# 1-Schematic_SIT210_PCB.net
KiCad netlist of a schematic drawn in EasyEDA
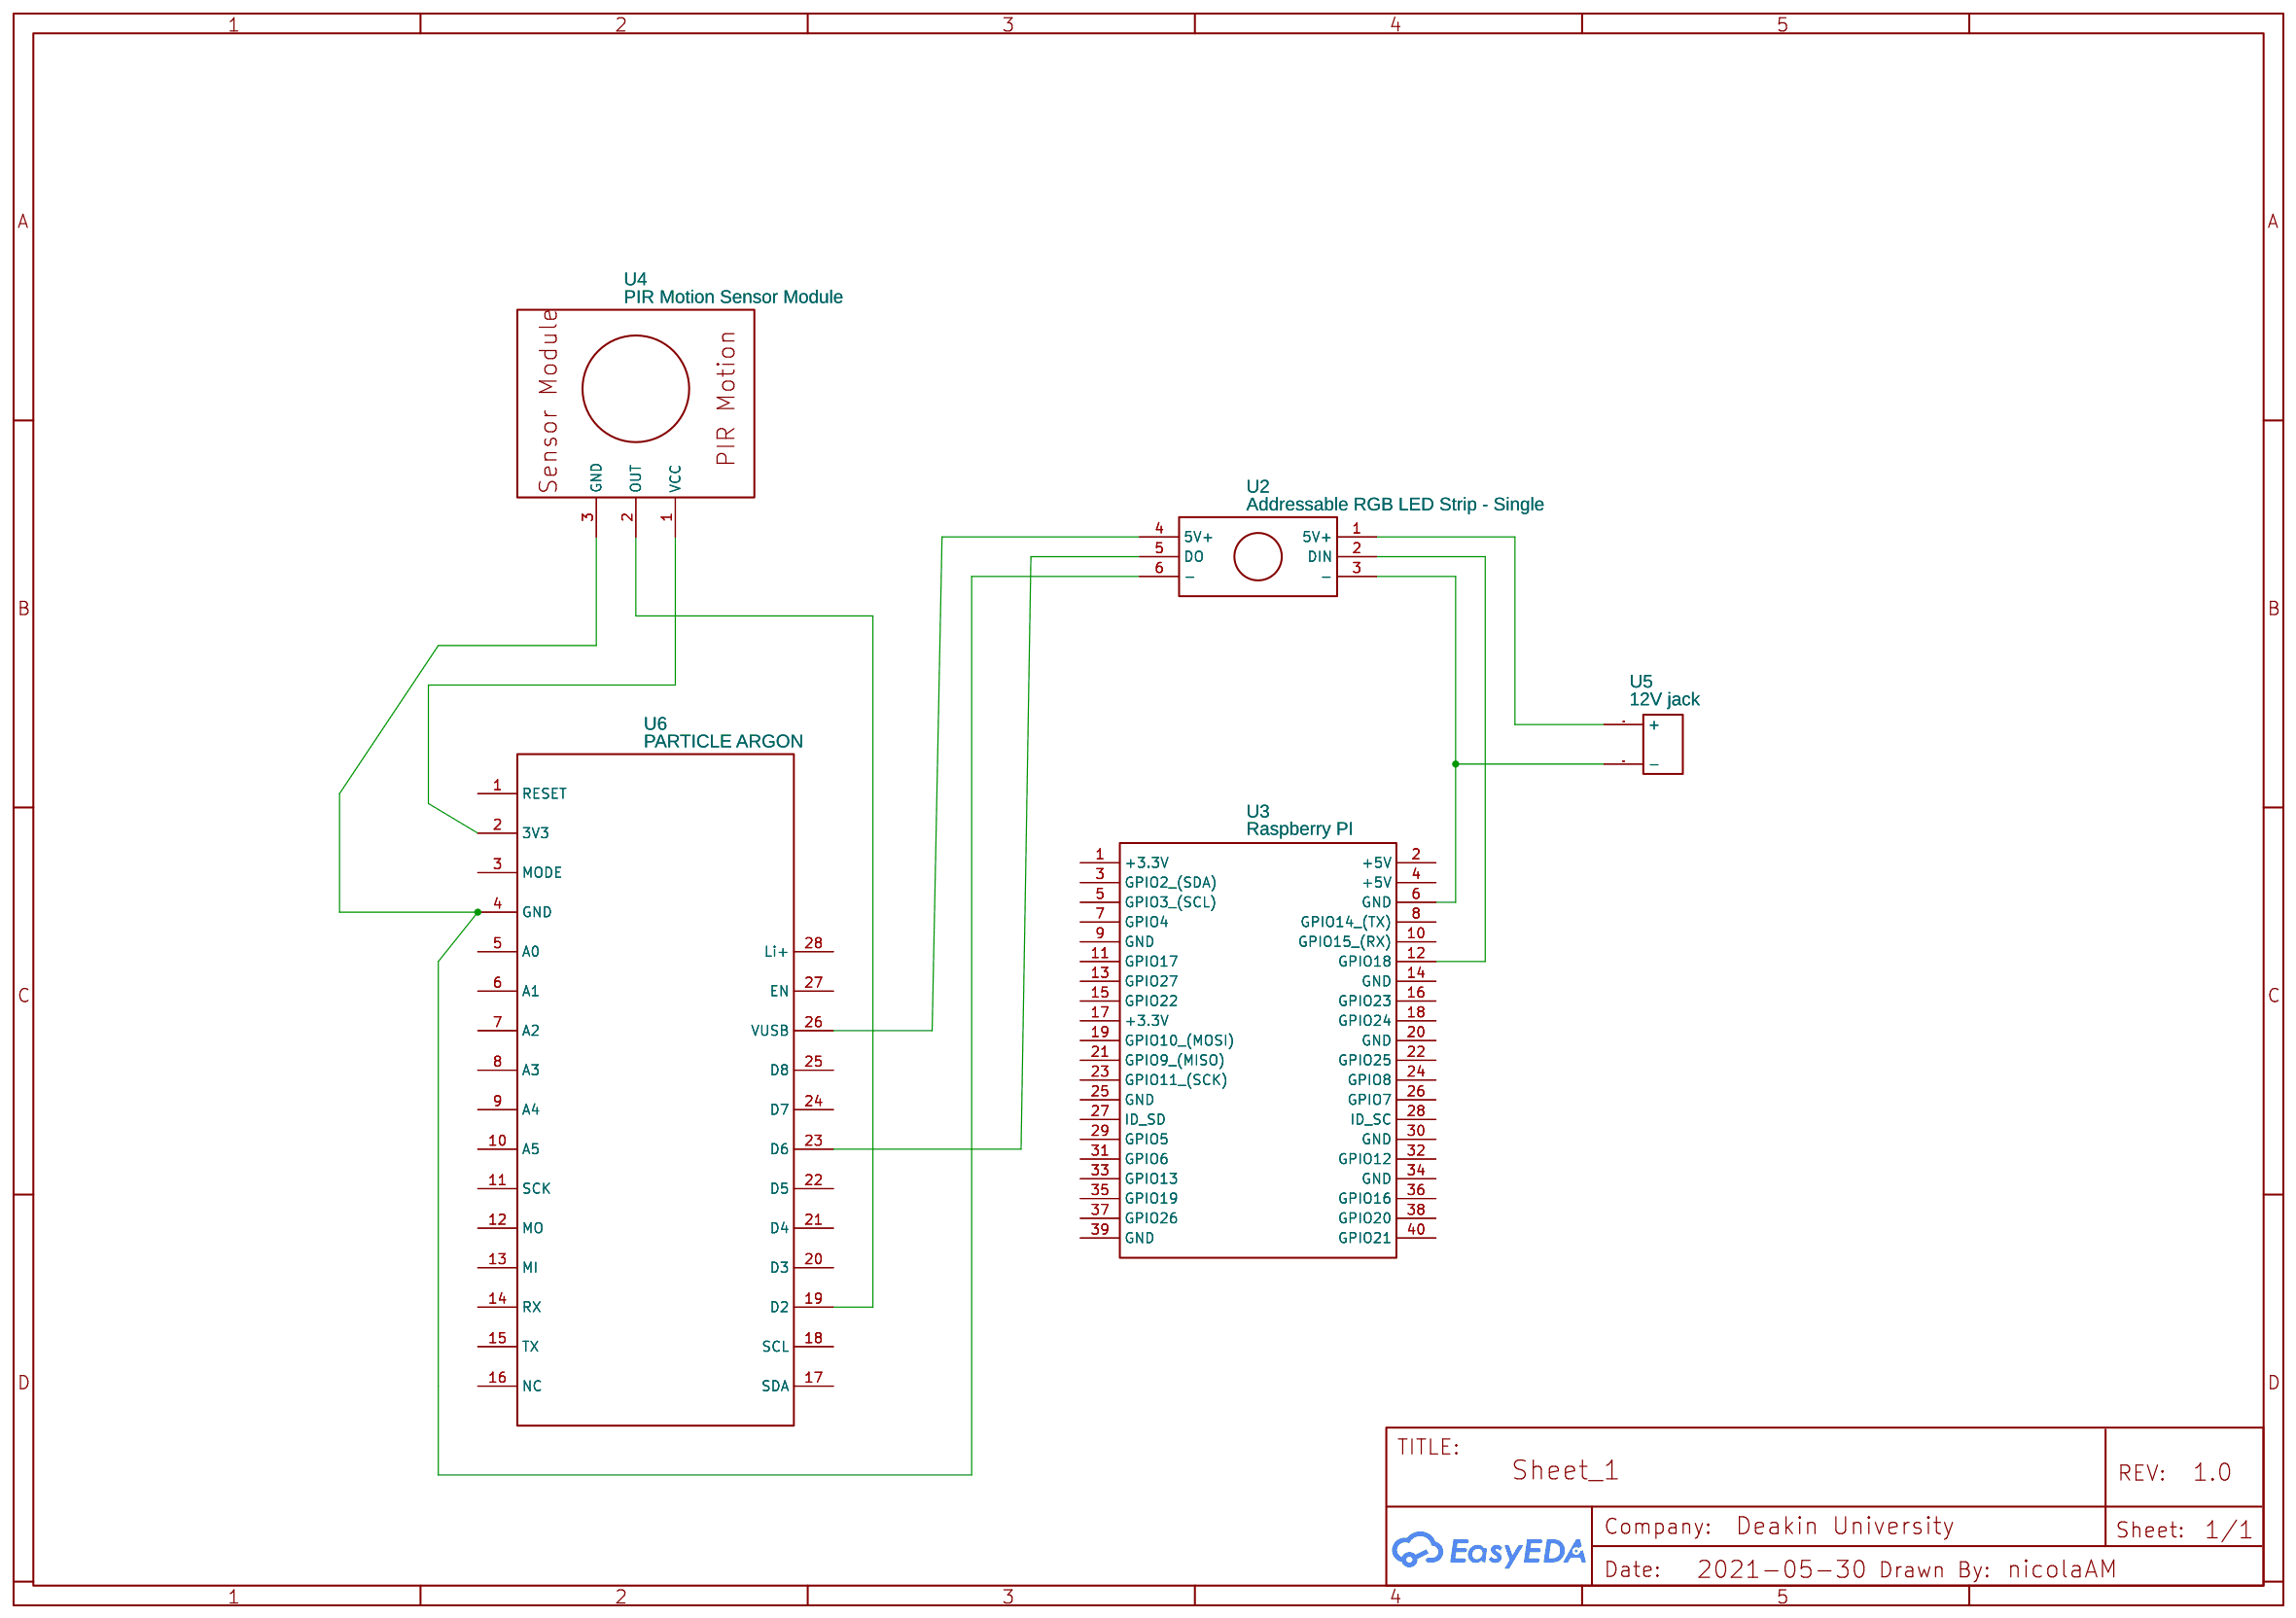
[diagram p0: schematic sheet]

(export (version "E")
  (design (tool "Eeschema 10.0.6"))
  (components
    (comp (ref "U2")
      (value "Addressable RGB LED Strip - Single")
      (libsource (lib "") (part "Addressable RGB LED Strip - Single"))
    )
    (comp (ref "U3") (value "Raspberry PI") (libsource (lib "") (part "Raspberry PI")))
    (comp (ref "U4")
      (value "PIR Motion Sensor Module")
      (libsource (lib "") (part "PIR Motion Sensor Module"))
    )
    (comp (ref "U5") (value "12V jack") (libsource (lib "") (part "12V jack")))
    (comp (ref "U6") (value "PARTICLE ARGON") (libsource (lib "") (part "PARTICLE ARGON")))
  )
  (nets
    (net (code "1") (name "Net-(U2-DIN)") (class "Default")
      (node (ref "U2") (pin "2") (pinfunction "DIN_2") (pintype "input"))
      (node (ref "U3") (pin "12") (pinfunction "GPIO18_12") (pintype "unspecified"))
    )
    (net (code "2") (name "Net-(U2-DO)") (class "Default")
      (node (ref "U2") (pin "5") (pinfunction "DO_5") (pintype "output"))
      (node (ref "U6") (pin "23") (pinfunction "D6_23") (pintype "unspecified"))
    )
    (net (code "3") (name "Net-(U4-GND)") (class "Default")
      (node (ref "U2") (pin "6") (pinfunction "-_6") (pintype "passive"))
      (node (ref "U4") (pin "3") (pinfunction "GND_3") (pintype "unspecified"))
      (node (ref "U6") (pin "4") (pinfunction "GND_4") (pintype "unspecified"))
    )
    (net (code "4") (name "Net-(U4-OUT)") (class "Default")
      (node (ref "U4") (pin "2") (pinfunction "OUT_2") (pintype "unspecified"))
      (node (ref "U6") (pin "19") (pinfunction "D2_19") (pintype "unspecified"))
    )
    (net (code "5") (name "Net-(U4-VCC)") (class "Default")
      (node (ref "U4") (pin "1") (pinfunction "VCC_1") (pintype "unspecified"))
      (node (ref "U6") (pin "2") (pinfunction "3V3_2") (pintype "unspecified"))
    )
    (net (code "6") (name "Net-(U5-+)") (class "Default")
      (node (ref "U2") (pin "1") (pinfunction "5V+_1") (pintype "passive"))
      (node (ref "U5") (pin "Vcc") (pinfunction "+_Vcc") (pintype "unspecified"))
    )
    (net (code "7") (name "Net-(U5--)") (class "Default")
      (node (ref "U2") (pin "3") (pinfunction "-_3") (pintype "passive"))
      (node (ref "U3") (pin "6") (pinfunction "GND_6") (pintype "passive"))
      (node (ref "U5") (pin "GND") (pinfunction "-_GND") (pintype "unspecified"))
    )
    (net (code "8") (name "Net-(U6-VUSB)") (class "Default")
      (node (ref "U2") (pin "4") (pinfunction "5V+_4") (pintype "passive"))
      (node (ref "U6") (pin "26") (pinfunction "VUSB_26") (pintype "unspecified"))
    )
    (net (code "9") (name "unconnected-(U3-+3.3V-Pad1)") (class "Default")
      (node (ref "U3") (pin "1") (pinfunction "+3.3V_1") (pintype "passive"))
    )
    (net (code "10") (name "unconnected-(U3-+3.3V-Pad17)") (class "Default")
      (node (ref "U3") (pin "17") (pinfunction "+3.3V_17") (pintype "passive"))
    )
    (net (code "11") (name "unconnected-(U3-+5V-Pad2)") (class "Default")
      (node (ref "U3") (pin "2") (pinfunction "+5V_2") (pintype "passive"))
    )
    (net (code "12") (name "unconnected-(U3-+5V-Pad4)") (class "Default")
      (node (ref "U3") (pin "4") (pinfunction "+5V_4") (pintype "passive"))
    )
    (net (code "13") (name "unconnected-(U3-GND-Pad9)") (class "Default")
      (node (ref "U3") (pin "9") (pinfunction "GND_9") (pintype "passive"))
    )
    (net (code "14") (name "unconnected-(U3-GND-Pad14)") (class "Default")
      (node (ref "U3") (pin "14") (pinfunction "GND_14") (pintype "passive"))
    )
    (net (code "15") (name "unconnected-(U3-GND-Pad20)") (class "Default")
      (node (ref "U3") (pin "20") (pinfunction "GND_20") (pintype "passive"))
    )
    (net (code "16") (name "unconnected-(U3-GND-Pad25)") (class "Default")
      (node (ref "U3") (pin "25") (pinfunction "GND_25") (pintype "passive"))
    )
    (net (code "17") (name "unconnected-(U3-GND-Pad30)") (class "Default")
      (node (ref "U3") (pin "30") (pinfunction "GND_30") (pintype "passive"))
    )
    (net (code "18") (name "unconnected-(U3-GND-Pad34)") (class "Default")
      (node (ref "U3") (pin "34") (pinfunction "GND_34") (pintype "passive"))
    )
    (net (code "19") (name "unconnected-(U3-GND-Pad39)") (class "Default")
      (node (ref "U3") (pin "39") (pinfunction "GND_39") (pintype "passive"))
    )
    (net (code "20") (name "unconnected-(U3-GPIO2_(SDA)-Pad3)") (class "Default")
      (node (ref "U3") (pin "3") (pinfunction "GPIO2_(SDA)_3") (pintype "unspecified"))
    )
    (net (code "21") (name "unconnected-(U3-GPIO3_(SCL)-Pad5)") (class "Default")
      (node (ref "U3") (pin "5") (pinfunction "GPIO3_(SCL)_5") (pintype "unspecified"))
    )
    (net (code "22") (name "unconnected-(U3-GPIO4-Pad7)") (class "Default")
      (node (ref "U3") (pin "7") (pinfunction "GPIO4_7") (pintype "unspecified"))
    )
    (net (code "23") (name "unconnected-(U3-GPIO5-Pad29)") (class "Default")
      (node (ref "U3") (pin "29") (pinfunction "GPIO5_29") (pintype "unspecified"))
    )
    (net (code "24") (name "unconnected-(U3-GPIO6-Pad31)") (class "Default")
      (node (ref "U3") (pin "31") (pinfunction "GPIO6_31") (pintype "unspecified"))
    )
    (net (code "25") (name "unconnected-(U3-GPIO7-Pad26)") (class "Default")
      (node (ref "U3") (pin "26") (pinfunction "GPIO7_26") (pintype "unspecified"))
    )
    (net (code "26") (name "unconnected-(U3-GPIO8-Pad24)") (class "Default")
      (node (ref "U3") (pin "24") (pinfunction "GPIO8_24") (pintype "unspecified"))
    )
    (net (code "27") (name "unconnected-(U3-GPIO9_(MISO)-Pad21)") (class "Default")
      (node (ref "U3") (pin "21") (pinfunction "GPIO9_(MISO)_21") (pintype "unspecified"))
    )
    (net (code "28") (name "unconnected-(U3-GPIO10_(MOSI)-Pad19)") (class "Default")
      (node (ref "U3") (pin "19") (pinfunction "GPIO10_(MOSI)_19") (pintype "unspecified"))
    )
    (net (code "29") (name "unconnected-(U3-GPIO11_(SCK)-Pad23)") (class "Default")
      (node (ref "U3") (pin "23") (pinfunction "GPIO11_(SCK)_23") (pintype "unspecified"))
    )
    (net (code "30") (name "unconnected-(U3-GPIO12-Pad32)") (class "Default")
      (node (ref "U3") (pin "32") (pinfunction "GPIO12_32") (pintype "unspecified"))
    )
    (net (code "31") (name "unconnected-(U3-GPIO13-Pad33)") (class "Default")
      (node (ref "U3") (pin "33") (pinfunction "GPIO13_33") (pintype "unspecified"))
    )
    (net (code "32") (name "unconnected-(U3-GPIO14_(TX)-Pad8)") (class "Default")
      (node (ref "U3") (pin "8") (pinfunction "GPIO14_(TX)_8") (pintype "unspecified"))
    )
    (net (code "33") (name "unconnected-(U3-GPIO15_(RX)-Pad10)") (class "Default")
      (node (ref "U3") (pin "10") (pinfunction "GPIO15_(RX)_10") (pintype "unspecified"))
    )
    (net (code "34") (name "unconnected-(U3-GPIO16-Pad36)") (class "Default")
      (node (ref "U3") (pin "36") (pinfunction "GPIO16_36") (pintype "unspecified"))
    )
    (net (code "35") (name "unconnected-(U3-GPIO17-Pad11)") (class "Default")
      (node (ref "U3") (pin "11") (pinfunction "GPIO17_11") (pintype "unspecified"))
    )
    (net (code "36") (name "unconnected-(U3-GPIO19-Pad35)") (class "Default")
      (node (ref "U3") (pin "35") (pinfunction "GPIO19_35") (pintype "unspecified"))
    )
    (net (code "37") (name "unconnected-(U3-GPIO20-Pad38)") (class "Default")
      (node (ref "U3") (pin "38") (pinfunction "GPIO20_38") (pintype "unspecified"))
    )
    (net (code "38") (name "unconnected-(U3-GPIO21-Pad40)") (class "Default")
      (node (ref "U3") (pin "40") (pinfunction "GPIO21_40") (pintype "unspecified"))
    )
    (net (code "39") (name "unconnected-(U3-GPIO22-Pad15)") (class "Default")
      (node (ref "U3") (pin "15") (pinfunction "GPIO22_15") (pintype "unspecified"))
    )
    (net (code "40") (name "unconnected-(U3-GPIO23-Pad16)") (class "Default")
      (node (ref "U3") (pin "16") (pinfunction "GPIO23_16") (pintype "unspecified"))
    )
    (net (code "41") (name "unconnected-(U3-GPIO24-Pad18)") (class "Default")
      (node (ref "U3") (pin "18") (pinfunction "GPIO24_18") (pintype "unspecified"))
    )
    (net (code "42") (name "unconnected-(U3-GPIO25-Pad22)") (class "Default")
      (node (ref "U3") (pin "22") (pinfunction "GPIO25_22") (pintype "unspecified"))
    )
    (net (code "43") (name "unconnected-(U3-GPIO26-Pad37)") (class "Default")
      (node (ref "U3") (pin "37") (pinfunction "GPIO26_37") (pintype "unspecified"))
    )
    (net (code "44") (name "unconnected-(U3-GPIO27-Pad13)") (class "Default")
      (node (ref "U3") (pin "13") (pinfunction "GPIO27_13") (pintype "unspecified"))
    )
    (net (code "45") (name "unconnected-(U3-ID_SC-Pad28)") (class "Default")
      (node (ref "U3") (pin "28") (pinfunction "ID_SC_28") (pintype "unspecified"))
    )
    (net (code "46") (name "unconnected-(U3-ID_SD-Pad27)") (class "Default")
      (node (ref "U3") (pin "27") (pinfunction "ID_SD_27") (pintype "unspecified"))
    )
    (net (code "47") (name "unconnected-(U6-A0-Pad5)") (class "Default")
      (node (ref "U6") (pin "5") (pinfunction "A0_5") (pintype "unspecified"))
    )
    (net (code "48") (name "unconnected-(U6-A1-Pad6)") (class "Default")
      (node (ref "U6") (pin "6") (pinfunction "A1_6") (pintype "unspecified"))
    )
    (net (code "49") (name "unconnected-(U6-A2-Pad7)") (class "Default")
      (node (ref "U6") (pin "7") (pinfunction "A2_7") (pintype "unspecified"))
    )
    (net (code "50") (name "unconnected-(U6-A3-Pad8)") (class "Default")
      (node (ref "U6") (pin "8") (pinfunction "A3_8") (pintype "unspecified"))
    )
    (net (code "51") (name "unconnected-(U6-A4-Pad9)") (class "Default")
      (node (ref "U6") (pin "9") (pinfunction "A4_9") (pintype "unspecified"))
    )
    (net (code "52") (name "unconnected-(U6-A5-Pad10)") (class "Default")
      (node (ref "U6") (pin "10") (pinfunction "A5_10") (pintype "unspecified"))
    )
    (net (code "53") (name "unconnected-(U6-D3-Pad20)") (class "Default")
      (node (ref "U6") (pin "20") (pinfunction "D3_20") (pintype "unspecified"))
    )
    (net (code "54") (name "unconnected-(U6-D4-Pad21)") (class "Default")
      (node (ref "U6") (pin "21") (pinfunction "D4_21") (pintype "unspecified"))
    )
    (net (code "55") (name "unconnected-(U6-D5-Pad22)") (class "Default")
      (node (ref "U6") (pin "22") (pinfunction "D5_22") (pintype "unspecified"))
    )
    (net (code "56") (name "unconnected-(U6-D7-Pad24)") (class "Default")
      (node (ref "U6") (pin "24") (pinfunction "D7_24") (pintype "unspecified"))
    )
    (net (code "57") (name "unconnected-(U6-D8-Pad25)") (class "Default")
      (node (ref "U6") (pin "25") (pinfunction "D8_25") (pintype "unspecified"))
    )
    (net (code "58") (name "unconnected-(U6-EN-Pad27)") (class "Default")
      (node (ref "U6") (pin "27") (pinfunction "EN_27") (pintype "unspecified"))
    )
    (net (code "59") (name "unconnected-(U6-Li+-Pad28)") (class "Default")
      (node (ref "U6") (pin "28") (pinfunction "Li+_28") (pintype "unspecified"))
    )
    (net (code "60") (name "unconnected-(U6-MI-Pad13)") (class "Default")
      (node (ref "U6") (pin "13") (pinfunction "MI_13") (pintype "unspecified"))
    )
    (net (code "61") (name "unconnected-(U6-MO-Pad12)") (class "Default")
      (node (ref "U6") (pin "12") (pinfunction "MO_12") (pintype "unspecified"))
    )
    (net (code "62") (name "unconnected-(U6-MODE-Pad3)") (class "Default")
      (node (ref "U6") (pin "3") (pinfunction "MODE_3") (pintype "unspecified"))
    )
    (net (code "63") (name "unconnected-(U6-NC-Pad16)") (class "Default")
      (node (ref "U6") (pin "16") (pinfunction "NC_16") (pintype "unspecified"))
    )
    (net (code "64") (name "unconnected-(U6-RESET-Pad1)") (class "Default")
      (node (ref "U6") (pin "1") (pinfunction "RESET_1") (pintype "unspecified"))
    )
    (net (code "65") (name "unconnected-(U6-RX-Pad14)") (class "Default")
      (node (ref "U6") (pin "14") (pinfunction "RX_14") (pintype "unspecified"))
    )
    (net (code "66") (name "unconnected-(U6-SCK-Pad11)") (class "Default")
      (node (ref "U6") (pin "11") (pinfunction "SCK_11") (pintype "unspecified"))
    )
    (net (code "67") (name "unconnected-(U6-SCL-Pad18)") (class "Default")
      (node (ref "U6") (pin "18") (pinfunction "SCL_18") (pintype "unspecified"))
    )
    (net (code "68") (name "unconnected-(U6-SDA-Pad17)") (class "Default")
      (node (ref "U6") (pin "17") (pinfunction "SDA_17") (pintype "unspecified"))
    )
    (net (code "69") (name "unconnected-(U6-TX-Pad15)") (class "Default")
      (node (ref "U6") (pin "15") (pinfunction "TX_15") (pintype "unspecified"))
    )
  )
)
